# Microcontroller.net
KiCad netlist of a schematic drawn in Altium Designer
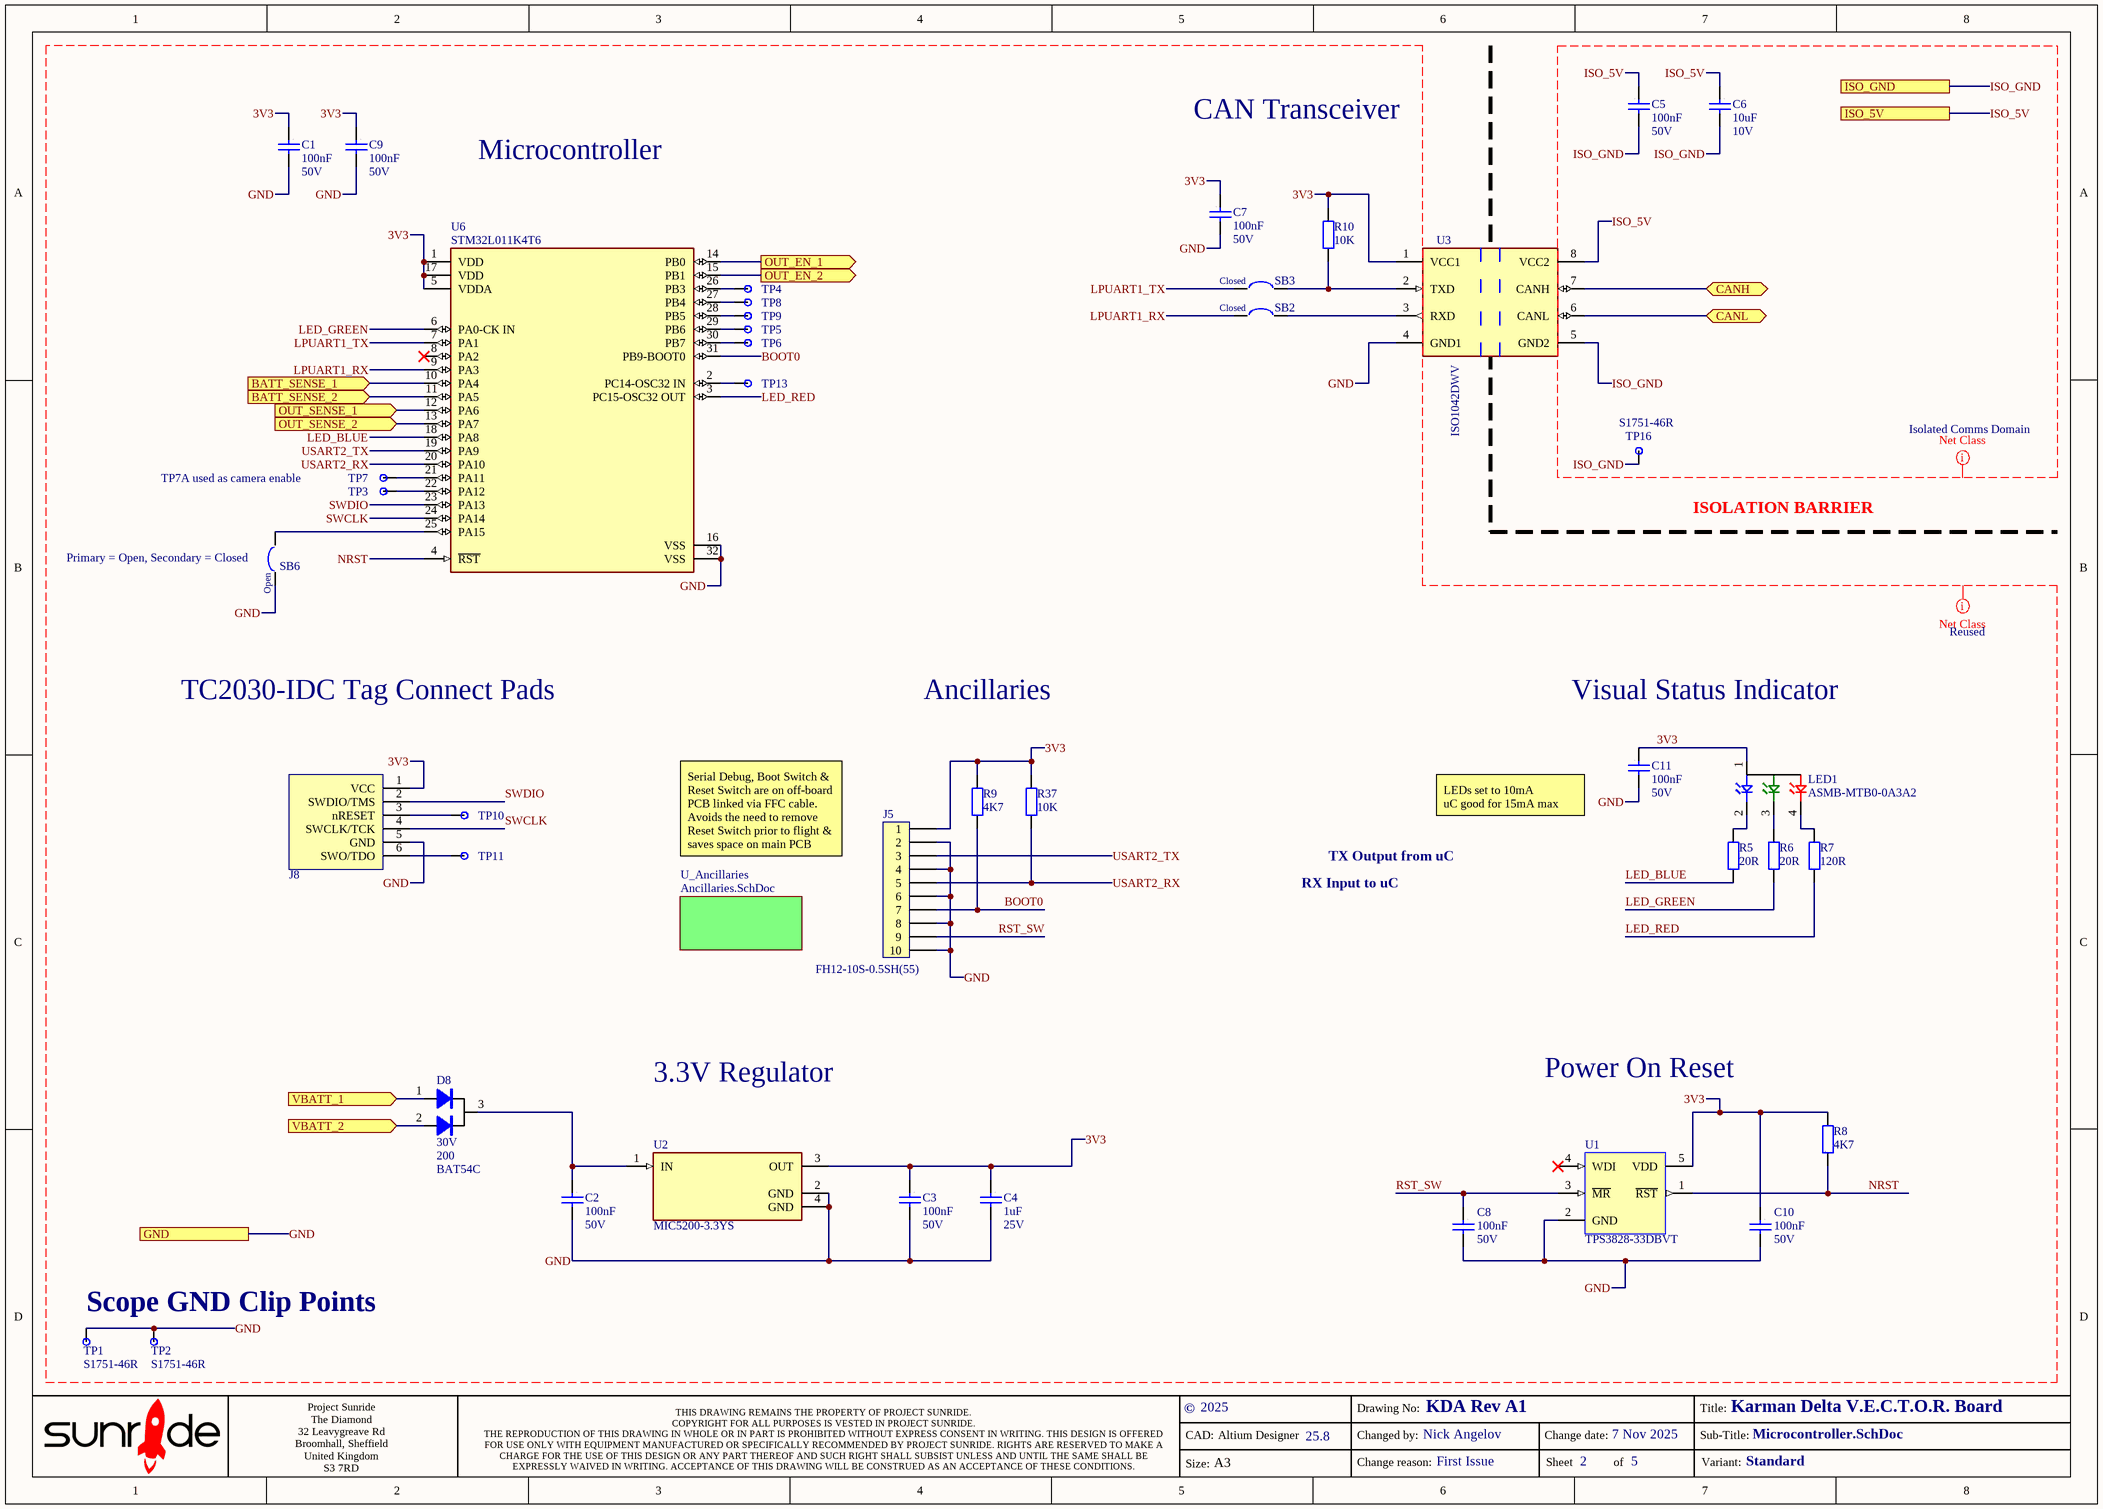
[diagram p0: Microcontroller.SchDoc]

(export (version "E")
  (design (tool "Eeschema 10.0.6"))
  (components
    (comp (ref "C1")
      (value "100nF")
      (footprint "CAPC1608X08L")
      (description "Capacitor MLC 100nF 50V X7R 10% CAPC1608X08M")
      (fields
        (field (name "VOLTAGE") "50V")
        (field (name "MANUFACTURER") "Murata")
        (field (name "MANUPARTNO") "GRM188R71H104KA93D")
      )
      (libsource (lib "") (part "CAP_1"))
    )
    (comp (ref "C2")
      (value "100nF")
      (footprint "CAPC1608X08L")
      (description "Capacitor MLC 100nF 50V X7R 10% CAPC1608X08M")
      (fields
        (field (name "VOLTAGE") "50V")
        (field (name "MANUFACTURER") "Murata")
        (field (name "MANUPARTNO") "GRM188R71H104KA93D")
      )
      (libsource (lib "") (part "CAP_1"))
    )
    (comp (ref "C3")
      (value "100nF")
      (footprint "CAPC1608X08L")
      (description "Capacitor MLC 100nF 50V X7R 10% CAPC1608X08M")
      (fields
        (field (name "VOLTAGE") "50V")
        (field (name "MANUFACTURER") "Murata")
        (field (name "MANUPARTNO") "GRM188R71H104KA93D")
      )
      (libsource (lib "") (part "CAP_1"))
    )
    (comp (ref "C4")
      (value "1uF")
      (footprint "CAPC1608X08L")
      (description "Capacitor MLC 1uF 25V X7R 10% CAPC1608X08M")
      (fields
        (field (name "VOLTAGE") "25V")
        (field (name "MANUFACTURER") "Samsung")
        (field (name "MANUPARTNO") "CL10B105KA8NFNC")
      )
      (libsource (lib "") (part "CAP_1"))
    )
    (comp (ref "C5")
      (value "100nF")
      (footprint "CAPC1608X08L")
      (description "Capacitor MLC 100nF 50V X7R 10% CAPC1608X08M")
      (fields
        (field (name "VOLTAGE") "50V")
        (field (name "MANUFACTURER") "Murata")
        (field (name "MANUPARTNO") "GRM188R71H104KA93D")
      )
      (libsource (lib "Library") (part "CAP"))
    )
    (comp (ref "C6")
      (value "10uF")
      (footprint "CAPC2012X15M")
      (description "Capacitor MLC 10uF10V X7R 10% CAPC2012X15M")
      (fields
        (field (name "VOLTAGE") "10V")
        (field (name "MANUFACTURER") "Murata")
        (field (name "MANUPARTNO") "GRM21BR71A106KE51L")
      )
      (libsource (lib "") (part "CAP_1"))
    )
    (comp (ref "C7")
      (value "100nF")
      (footprint "CAPC1608X08L")
      (description "Capacitor MLC 100nF 50V X7R 10% CAPC1608X08M")
      (fields
        (field (name "VOLTAGE") "50V")
        (field (name "MANUFACTURER") "Murata")
        (field (name "MANUPARTNO") "GRM188R71H104KA93D")
      )
      (libsource (lib "Library") (part "CAP"))
    )
    (comp (ref "C8")
      (value "100nF")
      (footprint "CAPC1608X08L")
      (description "Capacitor MLC 100nF 50V X7R 10% CAPC1608X08M")
      (fields
        (field (name "VOLTAGE") "50V")
        (field (name "MANUFACTURER") "Murata")
        (field (name "MANUPARTNO") "GRM188R71H104KA93D")
      )
      (libsource (lib "") (part "CAP_1"))
    )
    (comp (ref "C9")
      (value "100nF")
      (footprint "CAPC1608X08L")
      (description "Capacitor MLC 100nF 50V X7R 10% CAPC1608X08M")
      (fields
        (field (name "VOLTAGE") "50V")
        (field (name "MANUFACTURER") "Murata")
        (field (name "MANUPARTNO") "GRM188R71H104KA93D")
      )
      (libsource (lib "") (part "CAP_1"))
    )
    (comp (ref "C10")
      (value "100nF")
      (footprint "CAPC1608X08L")
      (description "Capacitor MLC 100nF 50V X7R 10% CAPC1608X08M")
      (fields
        (field (name "VOLTAGE") "50V")
        (field (name "MANUFACTURER") "Murata")
        (field (name "MANUPARTNO") "GRM188R71H104KA93D")
      )
      (libsource (lib "") (part "CAP_1"))
    )
    (comp (ref "C11")
      (value "100nF")
      (footprint "CAPC1608X08L")
      (description "Capacitor MLC 100nF 50V X7R 10% CAPC1608X08M")
      (fields
        (field (name "VOLTAGE") "50V")
        (field (name "MANUFACTURER") "Murata")
        (field (name "MANUPARTNO") "GRM188R71H104KA93D")
      )
      (libsource (lib "Library") (part "CAP"))
    )
    (comp (ref "D8")
      (value "*")
      (footprint "SOT95P237X112-3M")
      (description "Diode Schottky BAT54C SOT-23")
      (fields
        (field (name "VR (V)") "30V")
        (field (name "IF (MA)") "200")
        (field (name "MANUPARTNO") "BAT54C")
        (field (name "MANUFACTURER") "Fairchild")
      )
      (libsource (lib "Library") (part "DIODESOT23C"))
    )
    (comp (ref "J5")
      (value "Ancillaries")
      (footprint "FH12-10S-0_5SH")
      (description "Connector 10W FFC/FPC 0.5mm SM ZIF")
      (fields (field (name "MANUPARTNO") "FH12-10S-0.5SH(55)") (field (name "MANUFACTURER") "Hirose"))
      (libsource (lib "Library") (part "CON10"))
    )
    (comp (ref "J8")
      (value "TC2030-IDC Tag Connect Pads")
      (footprint "TC2030-IDC-NL")
      (description "TC2030 Tag Connect Programmer Connection - Non BOM part")
      (fields (field (name "MANUFACTURER") "Tag Connect"))
      (libsource (lib "Library") (part "TC2030-IDC"))
    )
    (comp (ref "LED1")
      (value "Visual Status Indicator")
      (footprint "ASMB-MTB0-0A3A2")
      (description "LED RGB, SMD, 2.4mm, 115 °")
      (fields (field (name "MANUPARTNO") "ASMB-MTB0-0A3A2") (field (name "MANUFACTURER") "Wurth"))
      (libsource (lib "Library") (part "LED_RGB"))
    )
    (comp (ref "R5")
      (value "20R")
      (footprint "RESC1608X06L")
      (description "Resistor 20R 1% 50V RESC1608X06M")
      (fields (field (name "VOLTAGE") "50V") (field (name "MANUFACTURER") "Multicomp"))
      (libsource (lib "Library") (part "RESISTOR"))
    )
    (comp (ref "R6")
      (value "20R")
      (footprint "RESC1608X06L")
      (description "Resistor 20R 1% 50V RESC1608X06M")
      (fields (field (name "VOLTAGE") "50V") (field (name "MANUFACTURER") "Multicomp"))
      (libsource (lib "Library") (part "RESISTOR"))
    )
    (comp (ref "R7")
      (value "120R")
      (footprint "RESC1608X06L")
      (description "Resistor 120R 1% 50V RESC1608X06M")
      (fields (field (name "VOLTAGE") "50V") (field (name "MANUFACTURER") "Multicomp"))
      (libsource (lib "Library") (part "RESISTOR"))
    )
    (comp (ref "R8")
      (value "4K7")
      (footprint "RESC1608X06L")
      (description "Resistor 4K7 1% 50V RESC1608X06M")
      (fields (field (name "VOLTAGE") "50V") (field (name "MANUFACTURER") "Multicomp"))
      (libsource (lib "Library") (part "RESISTOR"))
    )
    (comp (ref "R9")
      (value "4K7")
      (footprint "RESC1608X06L")
      (description "Resistor 4K7 1% 50V RESC1608X06M")
      (fields (field (name "VOLTAGE") "50V") (field (name "MANUFACTURER") "Multicomp"))
      (libsource (lib "Library") (part "RESISTOR"))
    )
    (comp (ref "R10")
      (value "10K")
      (footprint "RESC1608X06L")
      (description "SMD Chip Resistor, Thin Film, 10 kohm, 75 V, 0603 [1608 Metric], 100 mW, ± 0.1%, ERA3A Series")
      (fields (field (name "VOLTAGE") "75V") (field (name "MANUFACTURER") "Panasonic"))
      (libsource (lib "") (part "RESISTOR_1"))
    )
    (comp (ref "R37")
      (value "10K")
      (footprint "RESC1608X06L")
      (description "SMD Chip Resistor, Thin Film, 10 kohm, 75 V, 0603 [1608 Metric], 100 mW, ± 0.1%, ERA3A Series")
      (fields (field (name "VOLTAGE") "75V") (field (name "MANUFACTURER") "Panasonic"))
      (libsource (lib "") (part "RESISTOR_1"))
    )
    (comp (ref "SB2")
      (value "Solder Blob Closed")
      (footprint "0603SolderLinkClosed")
      (description "Solder Blob - Closed 0603 SM pads")
      (libsource (lib "Library") (part "Solder Blob Closed"))
    )
    (comp (ref "SB3")
      (value "Solder Blob Closed")
      (footprint "0603SolderLinkClosed")
      (description "Solder Blob - Closed 0603 SM pads")
      (libsource (lib "Library") (part "Solder Blob Closed"))
    )
    (comp (ref "SB6")
      (value "Primary = Open, Secondary = Closed")
      (footprint "0603SolderLinkOpen")
      (description "Solder Blob - Open 0603 SM pads")
      (libsource (lib "Library") (part "Solder Blob Open"))
    )
    (comp (ref "TP1")
      (value "GND")
      (footprint "S1751-46R")
      (description "PCB Test Point S1751 Series, Surface Mount")
      (fields (field (name "MANUPARTNO") "S1751-46R") (field (name "MANUFACTURER") "Harwin"))
      (libsource (lib "Library") (part "TP1-fitted"))
    )
    (comp (ref "TP2")
      (value "GND")
      (footprint "S1751-46R")
      (description "PCB Test Point S1751 Series, Surface Mount")
      (fields (field (name "MANUPARTNO") "S1751-46R") (field (name "MANUFACTURER") "Harwin"))
      (libsource (lib "Library") (part "TP1-fitted"))
    )
    (comp (ref "TP3")
      (value "TMS")
      (footprint "TP1")
      (description "Testpoint 1mm dia. Component side, no silk")
      (libsource (lib "Library") (part "TP1"))
    )
    (comp (ref "TP4")
      (value "TMS")
      (footprint "TP1")
      (description "Testpoint 1mm dia. Component side, no silk")
      (libsource (lib "Library") (part "TP1"))
    )
    (comp (ref "TP5")
      (value "TMS")
      (footprint "TP1")
      (description "Testpoint 1mm dia. Component side, no silk")
      (libsource (lib "Library") (part "TP1"))
    )
    (comp (ref "TP6")
      (value "TMS")
      (footprint "TP1")
      (description "Testpoint 1mm dia. Component side, no silk")
      (libsource (lib "Library") (part "TP1"))
    )
    (comp (ref "TP7")
      (value "TP7A used as camera enable")
      (footprint "TP1")
      (description "Testpoint 1mm dia. Component side, no silk")
      (libsource (lib "Library") (part "TP1"))
    )
    (comp (ref "TP8")
      (value "TMS")
      (footprint "TP1")
      (description "Testpoint 1mm dia. Component side, no silk")
      (libsource (lib "Library") (part "TP1"))
    )
    (comp (ref "TP9")
      (value "TMS")
      (footprint "TP1")
      (description "Testpoint 1mm dia. Component side, no silk")
      (libsource (lib "Library") (part "TP1"))
    )
    (comp (ref "TP10")
      (value "TMS")
      (footprint "TP1")
      (description "Testpoint 1mm dia. Component side, no silk")
      (libsource (lib "Library") (part "TP1"))
    )
    (comp (ref "TP11")
      (value "TMS")
      (footprint "TP1")
      (description "Testpoint 1mm dia. Component side, no silk")
      (libsource (lib "Library") (part "TP1"))
    )
    (comp (ref "TP13")
      (value "TMS")
      (footprint "TP1")
      (description "Testpoint 1mm dia. Component side, no silk")
      (libsource (lib "Library") (part "TP1"))
    )
    (comp (ref "TP16")
      (value "GND")
      (footprint "S1751-46R")
      (description "PCB Test Point S1751 Series, Surface Mount")
      (fields (field (name "MANUPARTNO") "S1751-46R") (field (name "MANUFACTURER") "Harwin"))
      (libsource (lib "Library") (part "TP1-fitted"))
    )
    (comp (ref "U1")
      (value "Power On Reset")
      (footprint "SOT95P280X145-5L")
      (description "IC Supply Voltage Monitor, 2.93V TPS3828-33DBVT SOT23-5")
      (fields (field (name "MANUPARTNO") "TPS3828-33DBVT") (field (name "MANUFACTURER") "Texas"))
      (libsource (lib "Library") (part "VSENSE5"))
    )
    (comp (ref "U2")
      (value "MIC5200-3.3YS")
      (footprint "FP-SOT223-3LD-PL-1-IPC_C")
      (description "IC REG LIN 3.3V 100MA SOT223-3")
      (libsource (lib "Altium Content Vault") (part "f5128a9f8ed94365bfd39dcb8083813"))
    )
    (comp (ref "U3")
      (value "CAN Transceiver")
      (footprint "FP-DWV0008A-IPC_C")
      (description "IC TRANSCEIVER FULL 1/1 8SOIC")
      (fields (field (name "MANUF PART NO") "ISO1042DWV"))
      (libsource (lib "Altium Content Vault") (part "909e5d76d32ef4d3bd4dfdc3f0018f8"))
    )
    (comp (ref "U6")
      (value "Microcontroller")
      (footprint "FP-LQFP32-5V-MFG")
      (description "IC MCU 32BIT 16KB FLASH 32LQFP")
      (fields
        (field (name "MANUFACTURER PART NUMBER") "STM32L011K4T6")
        (field (name "MANUFACTURER") "STMicroelectronics")
        (field (name "OCTOPART") "https://octopart.com/stm32l011k4t6-stmicroelectronics-71108062")
      )
      (libsource (lib "Altium Content Vault") (part "3cbf9028c7ade503566d0a55c35e94d"))
    )
  )
  (nets
    (net (code "1") (name "/3V3") (class "Default")
      (node (ref "C1") (pin "1") (pinfunction "1_1") (pintype "passive"))
      (node (ref "C10") (pin "1") (pinfunction "1_1") (pintype "passive"))
      (node (ref "C11") (pin "1") (pinfunction "1_1") (pintype "passive"))
      (node (ref "C3") (pin "1") (pinfunction "1_1") (pintype "passive"))
      (node (ref "C4") (pin "1") (pinfunction "1_1") (pintype "passive"))
      (node (ref "C7") (pin "1") (pinfunction "1_1") (pintype "passive"))
      (node (ref "C9") (pin "1") (pinfunction "1_1") (pintype "passive"))
      (node (ref "J5") (pin "1") (pinfunction "1_1") (pintype "passive"))
      (node (ref "J8") (pin "1") (pinfunction "VCC_1") (pintype "passive"))
      (node (ref "LED1") (pin "1") (pinfunction "A_1") (pintype "passive"))
      (node (ref "R10") (pin "2") (pinfunction "2_2") (pintype "passive"))
      (node (ref "R37") (pin "2") (pinfunction "2_2") (pintype "passive"))
      (node (ref "R8") (pin "2") (pinfunction "2_2") (pintype "passive"))
      (node (ref "R9") (pin "2") (pinfunction "2_2") (pintype "passive"))
      (node (ref "U1") (pin "5") (pinfunction "VDD_5") (pintype "power_in"))
      (node (ref "U2") (pin "3") (pinfunction "OUT_3") (pintype "power_in"))
      (node (ref "U3") (pin "1") (pinfunction "VCC1_1") (pintype "power_in"))
      (node (ref "U6") (pin "1") (pinfunction "VDD_1") (pintype "power_in"))
      (node (ref "U6") (pin "17") (pinfunction "VDD_17") (pintype "power_in"))
      (node (ref "U6") (pin "5") (pinfunction "VDDA_5") (pintype "power_in"))
    )
    (net (code "2") (name "/BATT_SENSE_1") (class "Default")
      (node (ref "U6") (pin "10") (pinfunction "PA4_10") (pintype "bidirectional"))
    )
    (net (code "3") (name "/BATT_SENSE_2") (class "Default")
      (node (ref "U6") (pin "11") (pinfunction "PA5_11") (pintype "bidirectional"))
    )
    (net (code "4") (name "/BOOT0") (class "Default")
      (node (ref "J5") (pin "7") (pinfunction "7_7") (pintype "passive"))
      (node (ref "R9") (pin "1") (pinfunction "1_1") (pintype "passive"))
      (node (ref "U6") (pin "31") (pinfunction "PB9-BOOT0_31") (pintype "bidirectional"))
    )
    (net (code "5") (name "/CANH") (class "Default")
      (node (ref "U3") (pin "7") (pinfunction "CANH_7") (pintype "bidirectional"))
    )
    (net (code "6") (name "/CANL") (class "Default")
      (node (ref "U3") (pin "6") (pinfunction "CANL_6") (pintype "bidirectional"))
    )
    (net (code "7") (name "/GND") (class "Default")
      (node (ref "C1") (pin "2") (pinfunction "2_2") (pintype "passive"))
      (node (ref "C10") (pin "2") (pinfunction "2_2") (pintype "passive"))
      (node (ref "C11") (pin "2") (pinfunction "2_2") (pintype "passive"))
      (node (ref "C2") (pin "2") (pinfunction "2_2") (pintype "passive"))
      (node (ref "C3") (pin "2") (pinfunction "2_2") (pintype "passive"))
      (node (ref "C4") (pin "2") (pinfunction "2_2") (pintype "passive"))
      (node (ref "C7") (pin "2") (pinfunction "2_2") (pintype "passive"))
      (node (ref "C8") (pin "2") (pinfunction "2_2") (pintype "passive"))
      (node (ref "C9") (pin "2") (pinfunction "2_2") (pintype "passive"))
      (node (ref "J5") (pin "10") (pinfunction "10_10") (pintype "passive"))
      (node (ref "J5") (pin "2") (pinfunction "2_2") (pintype "passive"))
      (node (ref "J5") (pin "4") (pinfunction "4_4") (pintype "passive"))
      (node (ref "J5") (pin "6") (pinfunction "6_6") (pintype "passive"))
      (node (ref "J5") (pin "8") (pinfunction "8_8") (pintype "passive"))
      (node (ref "J8") (pin "5") (pinfunction "GND_5") (pintype "passive"))
      (node (ref "SB6") (pin "1") (pinfunction "1_1") (pintype "passive"))
      (node (ref "TP1") (pin "1") (pintype "passive"))
      (node (ref "TP2") (pin "1") (pintype "passive"))
      (node (ref "U1") (pin "2") (pinfunction "GND_2") (pintype "passive"))
      (node (ref "U2") (pin "2") (pinfunction "GND_2") (pintype "power_in"))
      (node (ref "U2") (pin "4") (pinfunction "GND_4") (pintype "power_in"))
      (node (ref "U3") (pin "4") (pinfunction "GND1_4") (pintype "power_in"))
      (node (ref "U6") (pin "16") (pinfunction "VSS_16") (pintype "power_in"))
      (node (ref "U6") (pin "32") (pinfunction "VSS_32") (pintype "power_in"))
    )
    (net (code "8") (name "/ISO_5V") (class "Default")
      (node (ref "C5") (pin "1") (pinfunction "1_1") (pintype "passive"))
      (node (ref "C6") (pin "1") (pinfunction "1_1") (pintype "passive"))
      (node (ref "U3") (pin "8") (pinfunction "VCC2_8") (pintype "power_in"))
    )
    (net (code "9") (name "/ISO_GND") (class "Default")
      (node (ref "C5") (pin "2") (pinfunction "2_2") (pintype "passive"))
      (node (ref "C6") (pin "2") (pinfunction "2_2") (pintype "passive"))
      (node (ref "TP16") (pin "1") (pintype "passive"))
      (node (ref "U3") (pin "5") (pinfunction "GND2_5") (pintype "power_in"))
    )
    (net (code "10") (name "/LED_BLUE") (class "Default")
      (node (ref "R5") (pin "1") (pinfunction "1_1") (pintype "passive"))
      (node (ref "U6") (pin "18") (pinfunction "PA8_18") (pintype "bidirectional"))
    )
    (net (code "11") (name "/LED_GREEN") (class "Default")
      (node (ref "R6") (pin "1") (pinfunction "1_1") (pintype "passive"))
      (node (ref "U6") (pin "6") (pinfunction "PA0-CK_IN_6") (pintype "bidirectional"))
    )
    (net (code "12") (name "/LED_RED") (class "Default")
      (node (ref "R7") (pin "1") (pinfunction "1_1") (pintype "passive"))
      (node (ref "U6") (pin "3") (pinfunction "PC15-OSC32_OUT_3") (pintype "bidirectional"))
    )
    (net (code "13") (name "/LPUART1_RX") (class "Default")
      (node (ref "SB2") (pin "1") (pinfunction "1_1") (pintype "passive"))
      (node (ref "U6") (pin "9") (pinfunction "PA3_9") (pintype "bidirectional"))
    )
    (net (code "14") (name "/LPUART1_TX") (class "Default")
      (node (ref "SB3") (pin "1") (pinfunction "1_1") (pintype "passive"))
      (node (ref "U6") (pin "7") (pinfunction "PA1_7") (pintype "bidirectional"))
    )
    (net (code "15") (name "/NRST") (class "Default")
      (node (ref "R8") (pin "1") (pinfunction "1_1") (pintype "passive"))
      (node (ref "U1") (pin "1") (pinfunction "RST_1") (pintype "output"))
      (node (ref "U6") (pin "4") (pinfunction "~{RST}_4") (pintype "input"))
    )
    (net (code "16") (name "/OUT_EN_1") (class "Default")
      (node (ref "U6") (pin "14") (pinfunction "PB0_14") (pintype "bidirectional"))
    )
    (net (code "17") (name "/OUT_EN_2") (class "Default")
      (node (ref "U6") (pin "15") (pinfunction "PB1_15") (pintype "bidirectional"))
    )
    (net (code "18") (name "/OUT_SENSE_1") (class "Default")
      (node (ref "U6") (pin "12") (pinfunction "PA6_12") (pintype "bidirectional"))
    )
    (net (code "19") (name "/OUT_SENSE_2") (class "Default")
      (node (ref "U6") (pin "13") (pinfunction "PA7_13") (pintype "bidirectional"))
    )
    (net (code "20") (name "/RST_SW") (class "Default")
      (node (ref "C8") (pin "1") (pinfunction "1_1") (pintype "passive"))
      (node (ref "J5") (pin "9") (pinfunction "9_9") (pintype "passive"))
      (node (ref "U1") (pin "3") (pinfunction "MR_3") (pintype "input"))
    )
    (net (code "21") (name "/SWCLK") (class "Default")
      (node (ref "J8") (pin "4") (pinfunction "SWCLK/TCK_4") (pintype "passive"))
      (node (ref "U6") (pin "24") (pinfunction "PA14_24") (pintype "bidirectional"))
    )
    (net (code "22") (name "/SWDIO") (class "Default")
      (node (ref "J8") (pin "2") (pinfunction "SWDIO/TMS_2") (pintype "passive"))
      (node (ref "U6") (pin "23") (pinfunction "PA13_23") (pintype "bidirectional"))
    )
    (net (code "23") (name "/USART2_RX") (class "Default")
      (node (ref "J5") (pin "5") (pinfunction "5_5") (pintype "passive"))
      (node (ref "R37") (pin "1") (pinfunction "1_1") (pintype "passive"))
      (node (ref "U6") (pin "20") (pinfunction "PA10_20") (pintype "bidirectional"))
    )
    (net (code "24") (name "/USART2_TX") (class "Default")
      (node (ref "J5") (pin "3") (pinfunction "3_3") (pintype "passive"))
      (node (ref "U6") (pin "19") (pinfunction "PA9_19") (pintype "bidirectional"))
    )
    (net (code "25") (name "/VBATT_1") (class "Default")
      (node (ref "D8") (pin "1") (pinfunction "1_1") (pintype "passive"))
    )
    (net (code "26") (name "/VBATT_2") (class "Default")
      (node (ref "D8") (pin "2") (pinfunction "2_2") (pintype "passive"))
    )
    (net (code "27") (name "Net-(J8-SWO{slash}TDO)") (class "Default")
      (node (ref "J8") (pin "6") (pinfunction "SWO/TDO_6") (pintype "passive"))
      (node (ref "TP11") (pin "1") (pintype "passive"))
    )
    (net (code "28") (name "Net-(J8-nRESET)") (class "Default")
      (node (ref "J8") (pin "3") (pinfunction "nRESET_3") (pintype "passive"))
      (node (ref "TP10") (pin "1") (pintype "passive"))
    )
    (net (code "29") (name "Net-(LED1-B)") (class "Default")
      (node (ref "LED1") (pin "2") (pinfunction "B_2") (pintype "passive"))
      (node (ref "R5") (pin "2") (pinfunction "2_2") (pintype "passive"))
    )
    (net (code "30") (name "Net-(LED1-G)") (class "Default")
      (node (ref "LED1") (pin "3") (pinfunction "G_3") (pintype "passive"))
      (node (ref "R6") (pin "2") (pinfunction "2_2") (pintype "passive"))
    )
    (net (code "31") (name "Net-(LED1-R)") (class "Default")
      (node (ref "LED1") (pin "4") (pinfunction "R_4") (pintype "passive"))
      (node (ref "R7") (pin "2") (pinfunction "2_2") (pintype "passive"))
    )
    (net (code "32") (name "Net-(U2-IN)") (class "Default")
      (node (ref "C2") (pin "1") (pinfunction "1_1") (pintype "passive"))
      (node (ref "D8") (pin "3") (pinfunction "3_3") (pintype "passive"))
      (node (ref "U2") (pin "1") (pinfunction "IN_1") (pintype "input"))
    )
    (net (code "33") (name "Net-(U3-RXD)") (class "Default")
      (node (ref "SB2") (pin "2") (pinfunction "2_2") (pintype "passive"))
      (node (ref "U3") (pin "3") (pinfunction "RXD_3") (pintype "output"))
    )
    (net (code "34") (name "Net-(U3-TXD)") (class "Default")
      (node (ref "R10") (pin "1") (pinfunction "1_1") (pintype "passive"))
      (node (ref "SB3") (pin "2") (pinfunction "2_2") (pintype "passive"))
      (node (ref "U3") (pin "2") (pinfunction "TXD_2") (pintype "input"))
    )
    (net (code "35") (name "Net-(U6-PA11)") (class "Default")
      (node (ref "TP7") (pin "1") (pintype "passive"))
      (node (ref "U6") (pin "21") (pinfunction "PA11_21") (pintype "bidirectional"))
    )
    (net (code "36") (name "Net-(U6-PA12)") (class "Default")
      (node (ref "TP3") (pin "1") (pintype "passive"))
      (node (ref "U6") (pin "22") (pinfunction "PA12_22") (pintype "bidirectional"))
    )
    (net (code "37") (name "Net-(U6-PA15)") (class "Default")
      (node (ref "SB6") (pin "2") (pinfunction "2_2") (pintype "passive"))
      (node (ref "U6") (pin "25") (pinfunction "PA15_25") (pintype "bidirectional"))
    )
    (net (code "38") (name "Net-(U6-PB3)") (class "Default")
      (node (ref "TP4") (pin "1") (pintype "passive"))
      (node (ref "U6") (pin "26") (pinfunction "PB3_26") (pintype "bidirectional"))
    )
    (net (code "39") (name "Net-(U6-PB4)") (class "Default")
      (node (ref "TP8") (pin "1") (pintype "passive"))
      (node (ref "U6") (pin "27") (pinfunction "PB4_27") (pintype "bidirectional"))
    )
    (net (code "40") (name "Net-(U6-PB5)") (class "Default")
      (node (ref "TP9") (pin "1") (pintype "passive"))
      (node (ref "U6") (pin "28") (pinfunction "PB5_28") (pintype "bidirectional"))
    )
    (net (code "41") (name "Net-(U6-PB6)") (class "Default")
      (node (ref "TP5") (pin "1") (pintype "passive"))
      (node (ref "U6") (pin "29") (pinfunction "PB6_29") (pintype "bidirectional"))
    )
    (net (code "42") (name "Net-(U6-PB7)") (class "Default")
      (node (ref "TP6") (pin "1") (pintype "passive"))
      (node (ref "U6") (pin "30") (pinfunction "PB7_30") (pintype "bidirectional"))
    )
    (net (code "43") (name "Net-(U6-PC14-OSC32_IN)") (class "Default")
      (node (ref "TP13") (pin "1") (pintype "passive"))
      (node (ref "U6") (pin "2") (pinfunction "PC14-OSC32_IN_2") (pintype "bidirectional"))
    )
    (net (code "44") (name "unconnected-(U1-WDI-Pad4)") (class "Default")
      (node (ref "U1") (pin "4") (pinfunction "WDI_4") (pintype "input+no_connect"))
    )
    (net (code "45") (name "unconnected-(U6-PA2-Pad8)") (class "Default")
      (node (ref "U6") (pin "8") (pinfunction "PA2_8") (pintype "bidirectional+no_connect"))
    )
  )
)
